# design.net
KiCad netlist of a schematic drawn in Altium Designer
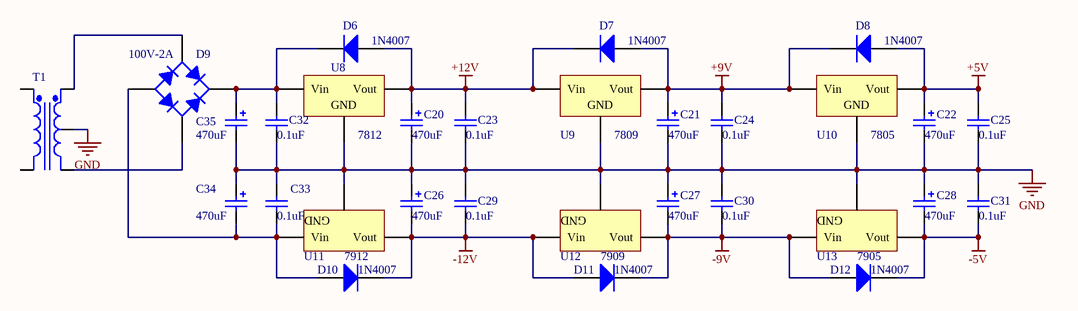
[diagram p0: 电源部分.SchDoc]

(export (version "E")
  (design (tool "Eeschema 10.0.6"))
  (components
    (comp (ref "C20")
      (value "~")
      (footprint "电解电容")
      (fields (field (name "ALTIUM_UNNAMED_1") "470uF"))
      (libsource (lib "自制库（原理图文件）") (part "电解电容"))
    )
    (comp (ref "C21")
      (value "~")
      (footprint "电解电容")
      (fields (field (name "ALTIUM_UNNAMED_1") "470uF"))
      (libsource (lib "自制库（原理图文件）") (part "电解电容"))
    )
    (comp (ref "C22")
      (value "~")
      (footprint "电解电容")
      (fields (field (name "ALTIUM_UNNAMED_1") "470uF"))
      (libsource (lib "自制库（原理图文件）") (part "电解电容"))
    )
    (comp (ref "C23")
      (value "瓷片电容")
      (footprint "瓷片电容")
      (fields (field (name "ALTIUM_UNNAMED_1") "0.1uF"))
      (libsource (lib "自制库（原理图文件）") (part "瓷片电容"))
    )
    (comp (ref "C24")
      (value "瓷片电容")
      (footprint "瓷片电容")
      (fields (field (name "ALTIUM_UNNAMED_1") "0.1uF"))
      (libsource (lib "自制库（原理图文件）") (part "瓷片电容"))
    )
    (comp (ref "C25")
      (value "瓷片电容")
      (footprint "瓷片电容")
      (fields (field (name "ALTIUM_UNNAMED_1") "0.1uF"))
      (libsource (lib "自制库（原理图文件）") (part "瓷片电容"))
    )
    (comp (ref "C26")
      (value "~")
      (footprint "电解电容")
      (fields (field (name "ALTIUM_UNNAMED_1") "470uF"))
      (libsource (lib "自制库（原理图文件）") (part "电解电容"))
    )
    (comp (ref "C27")
      (value "~")
      (footprint "电解电容")
      (fields (field (name "ALTIUM_UNNAMED_1") "470uF"))
      (libsource (lib "自制库（原理图文件）") (part "电解电容"))
    )
    (comp (ref "C28")
      (value "~")
      (footprint "电解电容")
      (fields (field (name "ALTIUM_UNNAMED_1") "470uF"))
      (libsource (lib "自制库（原理图文件）") (part "电解电容"))
    )
    (comp (ref "C29")
      (value "瓷片电容")
      (footprint "瓷片电容")
      (fields (field (name "ALTIUM_UNNAMED_1") "0.1uF"))
      (libsource (lib "自制库（原理图文件）") (part "瓷片电容"))
    )
    (comp (ref "C30")
      (value "瓷片电容")
      (footprint "瓷片电容")
      (fields (field (name "ALTIUM_UNNAMED_1") "0.1uF"))
      (libsource (lib "自制库（原理图文件）") (part "瓷片电容"))
    )
    (comp (ref "C31")
      (value "瓷片电容")
      (footprint "瓷片电容")
      (fields (field (name "ALTIUM_UNNAMED_1") "0.1uF"))
      (libsource (lib "自制库（原理图文件）") (part "瓷片电容"))
    )
    (comp (ref "C32")
      (value "瓷片电容")
      (footprint "瓷片电容")
      (fields (field (name "ALTIUM_UNNAMED_1") "0.1uF"))
      (libsource (lib "自制库（原理图文件）") (part "瓷片电容"))
    )
    (comp (ref "C33")
      (value "瓷片电容")
      (footprint "瓷片电容")
      (fields (field (name "ALTIUM_UNNAMED_1") "0.1uF"))
      (libsource (lib "自制库（原理图文件）") (part "瓷片电容"))
    )
    (comp (ref "C34")
      (value "~")
      (footprint "电解电容")
      (fields (field (name "ALTIUM_UNNAMED_1") "470uF"))
      (libsource (lib "自制库（原理图文件）") (part "电解电容"))
    )
    (comp (ref "C35")
      (value "~")
      (footprint "电解电容")
      (fields (field (name "ALTIUM_UNNAMED_1") "470uF"))
      (libsource (lib "自制库（原理图文件）") (part "电解电容"))
    )
    (comp (ref "D6")
      (value "1N4007")
      (footprint "DO-41")
      (description "1 Amp General Purpose Rectifier")
      (fields (field (name "PUBLISHER") "Altium Limited"))
      (libsource (lib "Miscellaneous Devices") (part "Diode 1N4007"))
    )
    (comp (ref "D7")
      (value "1N4007")
      (footprint "DO-41")
      (description "1 Amp General Purpose Rectifier")
      (fields (field (name "PUBLISHER") "Altium Limited"))
      (libsource (lib "Miscellaneous Devices") (part "Diode 1N4007"))
    )
    (comp (ref "D8")
      (value "1N4007")
      (footprint "DO-41")
      (description "1 Amp General Purpose Rectifier")
      (fields (field (name "PUBLISHER") "Altium Limited"))
      (libsource (lib "Miscellaneous Devices") (part "Diode 1N4007"))
    )
    (comp (ref "D9")
      (value "100V-2A")
      (footprint "D-38")
      (description "Full Wave Diode Bridge")
      (fields (field (name "PUBLISHER") "Altium Limited"))
      (libsource (lib "Miscellaneous Devices") (part "Bridge1"))
    )
    (comp (ref "D10")
      (value "1N4007")
      (footprint "DO-41")
      (description "1 Amp General Purpose Rectifier")
      (fields (field (name "PUBLISHER") "Altium Limited"))
      (libsource (lib "Miscellaneous Devices") (part "Diode 1N4007"))
    )
    (comp (ref "D11")
      (value "1N4007")
      (footprint "DO-41")
      (description "1 Amp General Purpose Rectifier")
      (fields (field (name "PUBLISHER") "Altium Limited"))
      (libsource (lib "Miscellaneous Devices") (part "Diode 1N4007"))
    )
    (comp (ref "D12")
      (value "1N4007")
      (footprint "DO-41")
      (description "1 Amp General Purpose Rectifier")
      (fields (field (name "PUBLISHER") "Altium Limited"))
      (libsource (lib "Miscellaneous Devices") (part "Diode 1N4007"))
    )
    (comp (ref "T1")
      (value "Trans CT")
      (footprint "TRF_5")
      (description "Center-Tapped Transformer (Coupled Inductor Model)")
      (fields (field (name "PUBLISHER") "Altium Limited"))
      (libsource (lib "Miscellaneous Devices") (part "Trans CT"))
    )
    (comp (ref "U8")
      (value "7812")
      (footprint "78**")
      (description "Voltage Regulator")
      (fields (field (name "PUBLISHER") "Altium Limited"))
      (libsource (lib "Miscellaneous Devices") (part "Volt Reg"))
    )
    (comp (ref "U9")
      (value "7809")
      (footprint "自制库（PCB）:78**")
      (description "Voltage Regulator")
      (fields (field (name "PUBLISHER") "Altium Limited"))
      (libsource (lib "Miscellaneous Devices") (part "Volt Reg"))
    )
    (comp (ref "U10")
      (value "7805")
      (footprint "78**")
      (description "Voltage Regulator")
      (fields (field (name "PUBLISHER") "Altium Limited"))
      (libsource (lib "Miscellaneous Devices") (part "Volt Reg"))
    )
    (comp (ref "U11")
      (value "7912")
      (footprint "79**")
      (description "Voltage Regulator")
      (fields (field (name "PUBLISHER") "Altium Limited"))
      (libsource (lib "") (part "Volt Reg_1"))
    )
    (comp (ref "U12")
      (value "7909")
      (footprint "79**")
      (description "Voltage Regulator")
      (fields (field (name "PUBLISHER") "Altium Limited"))
      (libsource (lib "") (part "Volt Reg_1"))
    )
    (comp (ref "U13")
      (value "7905")
      (footprint "79**")
      (description "Voltage Regulator")
      (fields (field (name "PUBLISHER") "Altium Limited"))
      (libsource (lib "") (part "Volt Reg_1"))
    )
  )
  (nets
    (net (code "1") (name "+5V") (class "Default")
      (node (ref "C22") (pin "1") (pinfunction "1_1") (pintype "passive"))
      (node (ref "C25") (pin "2") (pinfunction "2_2") (pintype "passive"))
      (node (ref "D8") (pin "1") (pinfunction "A_1") (pintype "passive"))
      (node (ref "U10") (pin "3") (pinfunction "Vout_3") (pintype "passive"))
    )
    (net (code "2") (name "+9V") (class "Default")
      (node (ref "C21") (pin "1") (pinfunction "1_1") (pintype "passive"))
      (node (ref "C24") (pin "2") (pinfunction "2_2") (pintype "passive"))
      (node (ref "D7") (pin "1") (pinfunction "A_1") (pintype "passive"))
      (node (ref "D8") (pin "2") (pinfunction "K_2") (pintype "passive"))
      (node (ref "U10") (pin "1") (pinfunction "Vin_1") (pintype "passive"))
      (node (ref "U9") (pin "3") (pinfunction "Vout_3") (pintype "passive"))
    )
    (net (code "3") (name "+12V") (class "Default")
      (node (ref "C20") (pin "1") (pinfunction "1_1") (pintype "passive"))
      (node (ref "C23") (pin "2") (pinfunction "2_2") (pintype "passive"))
      (node (ref "D6") (pin "1") (pinfunction "A_1") (pintype "passive"))
      (node (ref "D7") (pin "2") (pinfunction "K_2") (pintype "passive"))
      (node (ref "U8") (pin "3") (pinfunction "Vout_3") (pintype "passive"))
      (node (ref "U9") (pin "1") (pinfunction "Vin_1") (pintype "passive"))
    )
    (net (code "4") (name "-5V") (class "Default")
      (node (ref "C28") (pin "2") (pinfunction "2_2") (pintype "passive"))
      (node (ref "C31") (pin "1") (pinfunction "1_1") (pintype "passive"))
      (node (ref "D12") (pin "2") (pinfunction "K_2") (pintype "passive"))
      (node (ref "U13") (pin "3") (pinfunction "Vout_3") (pintype "passive"))
    )
    (net (code "5") (name "-9V") (class "Default")
      (node (ref "C27") (pin "2") (pinfunction "2_2") (pintype "passive"))
      (node (ref "C30") (pin "1") (pinfunction "1_1") (pintype "passive"))
      (node (ref "D11") (pin "2") (pinfunction "K_2") (pintype "passive"))
      (node (ref "D12") (pin "1") (pinfunction "A_1") (pintype "passive"))
      (node (ref "U12") (pin "3") (pinfunction "Vout_3") (pintype "passive"))
      (node (ref "U13") (pin "1") (pinfunction "Vin_1") (pintype "passive"))
    )
    (net (code "6") (name "-12V") (class "Default")
      (node (ref "C26") (pin "2") (pinfunction "2_2") (pintype "passive"))
      (node (ref "C29") (pin "1") (pinfunction "1_1") (pintype "passive"))
      (node (ref "D10") (pin "2") (pinfunction "K_2") (pintype "passive"))
      (node (ref "D11") (pin "1") (pinfunction "A_1") (pintype "passive"))
      (node (ref "U11") (pin "3") (pinfunction "Vout_3") (pintype "passive"))
      (node (ref "U12") (pin "1") (pinfunction "Vin_1") (pintype "passive"))
    )
    (net (code "7") (name "GND") (class "Default")
      (node (ref "C20") (pin "2") (pinfunction "2_2") (pintype "passive"))
      (node (ref "C21") (pin "2") (pinfunction "2_2") (pintype "passive"))
      (node (ref "C22") (pin "2") (pinfunction "2_2") (pintype "passive"))
      (node (ref "C23") (pin "1") (pinfunction "1_1") (pintype "passive"))
      (node (ref "C24") (pin "1") (pinfunction "1_1") (pintype "passive"))
      (node (ref "C25") (pin "1") (pinfunction "1_1") (pintype "passive"))
      (node (ref "C26") (pin "1") (pinfunction "1_1") (pintype "passive"))
      (node (ref "C27") (pin "1") (pinfunction "1_1") (pintype "passive"))
      (node (ref "C28") (pin "1") (pinfunction "1_1") (pintype "passive"))
      (node (ref "C29") (pin "2") (pinfunction "2_2") (pintype "passive"))
      (node (ref "C30") (pin "2") (pinfunction "2_2") (pintype "passive"))
      (node (ref "C31") (pin "2") (pinfunction "2_2") (pintype "passive"))
      (node (ref "C32") (pin "1") (pinfunction "1_1") (pintype "passive"))
      (node (ref "C33") (pin "2") (pinfunction "2_2") (pintype "passive"))
      (node (ref "C34") (pin "1") (pinfunction "1_1") (pintype "passive"))
      (node (ref "C35") (pin "2") (pinfunction "2_2") (pintype "passive"))
      (node (ref "T1") (pin "4") (pinfunction "SecCT_4") (pintype "passive"))
      (node (ref "U10") (pin "2") (pinfunction "GND_2") (pintype "passive"))
      (node (ref "U11") (pin "2") (pinfunction "GND_2") (pintype "passive"))
      (node (ref "U12") (pin "2") (pinfunction "GND_2") (pintype "passive"))
      (node (ref "U13") (pin "2") (pinfunction "GND_2") (pintype "passive"))
      (node (ref "U8") (pin "2") (pinfunction "GND_2") (pintype "passive"))
      (node (ref "U9") (pin "2") (pinfunction "GND_2") (pintype "passive"))
    )
    (net (code "8") (name "Net-(D6-K)") (class "Default")
      (node (ref "C32") (pin "2") (pinfunction "2_2") (pintype "passive"))
      (node (ref "C35") (pin "1") (pinfunction "1_1") (pintype "passive"))
      (node (ref "D6") (pin "2") (pinfunction "K_2") (pintype "passive"))
      (node (ref "D9") (pin "3") (pinfunction "K_3") (pintype "passive"))
      (node (ref "U8") (pin "1") (pinfunction "Vin_1") (pintype "passive"))
    )
    (net (code "9") (name "Net-(D10-A)") (class "Default")
      (node (ref "C33") (pin "1") (pinfunction "1_1") (pintype "passive"))
      (node (ref "C34") (pin "2") (pinfunction "2_2") (pintype "passive"))
      (node (ref "D10") (pin "1") (pinfunction "A_1") (pintype "passive"))
      (node (ref "D9") (pin "1") (pinfunction "A_1") (pintype "passive"))
      (node (ref "U11") (pin "1") (pinfunction "Vin_1") (pintype "passive"))
    )
    (net (code "10") (name "Net-(T1-Sec+)") (class "Default")
      (node (ref "D9") (pin "2") (pinfunction "C_2") (pintype "passive"))
      (node (ref "T1") (pin "3") (pinfunction "Sec+_3") (pintype "passive"))
    )
    (net (code "11") (name "Net-(T1-Sec-)") (class "Default")
      (node (ref "D9") (pin "4") (pinfunction "C_4") (pintype "passive"))
      (node (ref "T1") (pin "5") (pinfunction "Sec-_5") (pintype "passive"))
    )
    (net (code "12") (name "unconnected-(T1-Pri+-Pad1)") (class "Default")
      (node (ref "T1") (pin "1") (pinfunction "Pri+_1") (pintype "passive"))
    )
    (net (code "13") (name "unconnected-(T1-Pri--Pad2)") (class "Default")
      (node (ref "T1") (pin "2") (pinfunction "Pri-_2") (pintype "passive"))
    )
  )
)
